# 1_PowerSupply.net
KiCad netlist of a schematic drawn in Altium Designer
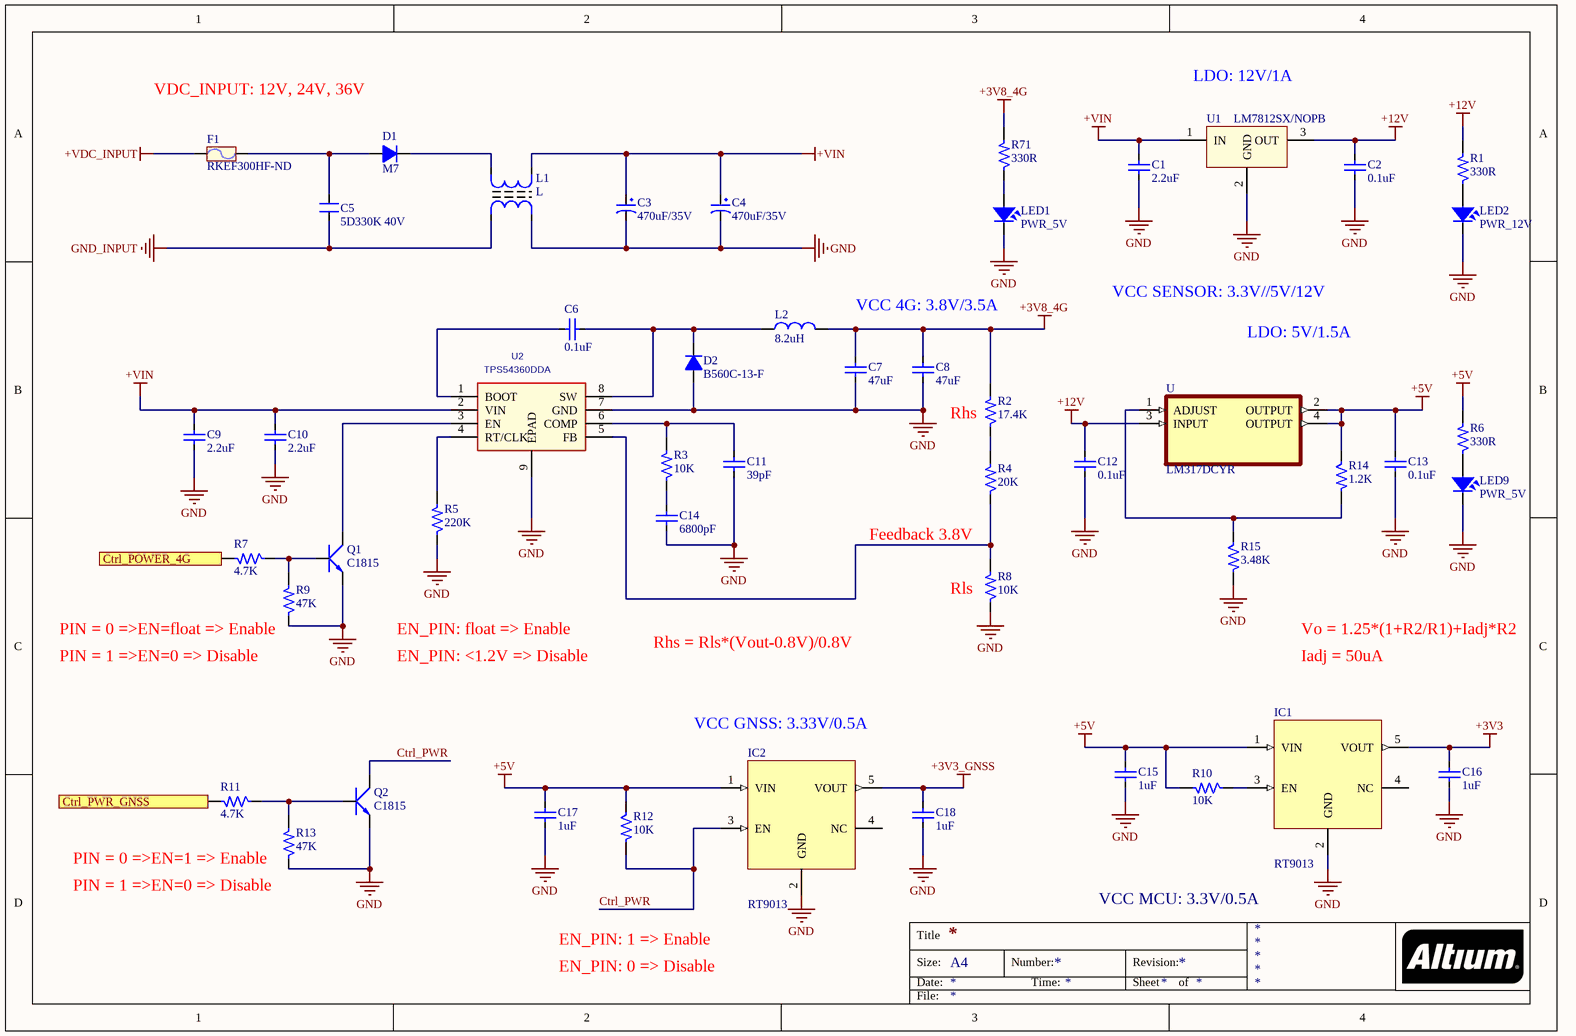
[diagram p0: [1]PowerSupply.SchDoc]

(export (version "E")
  (design (tool "Eeschema 10.0.6"))
  (components
    (comp (ref "C1")
      (value "2.2uF")
      (footprint "CAP_0805")
      (description "Capacitor")
      (fields (field (name "PUBLISHER") "Altium Limited"))
      (libsource (lib "My Library") (part "CapSMD"))
    )
    (comp (ref "C2")
      (value "0.1uF")
      (footprint "CAP_0805")
      (description "Capacitor")
      (fields (field (name "PUBLISHER") "Altium Limited"))
      (libsource (lib "My Library") (part "CapSMD"))
    )
    (comp (ref "C3")
      (value "470uF/35V")
      (footprint "C10mm")
      (description "Cap 1000uF/16V - 220uF/50V")
      (libsource (lib "GPS_Traking_V1_1") (part "CP4"))
    )
    (comp (ref "C4")
      (value "470uF/35V")
      (footprint "C10mm")
      (description "Cap 1000uF/16V - 220uF/50V")
      (libsource (lib "GPS_Traking_V1_1") (part "CP4"))
    )
    (comp (ref "C5")
      (value "5D330K 40V")
      (footprint "CN2")
      (description "5D330K 33V")
      (fields (field (name "DESIGNED BY") "VanDungEvn"))
      (libsource (lib "GPS_Traking_V1_1") (part "CN"))
    )
    (comp (ref "C6")
      (value "0.1uF")
      (footprint "CAP_0805")
      (description "Capacitor")
      (fields (field (name "PUBLISHER") "Altium Limited"))
      (libsource (lib "My Library") (part "CapSMD"))
    )
    (comp (ref "C7")
      (value "47uF")
      (footprint "CAP_0805")
      (description "Capacitor")
      (fields (field (name "PUBLISHER") "Altium Limited"))
      (libsource (lib "My Library") (part "CapSMD"))
    )
    (comp (ref "C8")
      (value "47uF")
      (footprint "CAP_0805")
      (description "Capacitor")
      (fields (field (name "PUBLISHER") "Altium Limited"))
      (libsource (lib "My Library") (part "CapSMD"))
    )
    (comp (ref "C9")
      (value "2.2uF")
      (footprint "CAP_0805")
      (description "Capacitor")
      (fields (field (name "PUBLISHER") "Altium Limited"))
      (libsource (lib "My Library") (part "CapSMD"))
    )
    (comp (ref "C10")
      (value "2.2uF")
      (footprint "CAP_0805")
      (description "Capacitor")
      (fields (field (name "PUBLISHER") "Altium Limited"))
      (libsource (lib "My Library") (part "CapSMD"))
    )
    (comp (ref "C11")
      (value "39pF")
      (footprint "CAP_0805")
      (description "Capacitor")
      (fields (field (name "PUBLISHER") "Altium Limited"))
      (libsource (lib "My Library") (part "CapSMD"))
    )
    (comp (ref "C12")
      (value "0.1uF")
      (footprint "CAP_0805")
      (description "Capacitor")
      (fields (field (name "PUBLISHER") "Altium Limited"))
      (libsource (lib "My Library") (part "CapSMD"))
    )
    (comp (ref "C13")
      (value "0.1uF")
      (footprint "CAP_0805")
      (description "Capacitor")
      (fields (field (name "PUBLISHER") "Altium Limited"))
      (libsource (lib "My Library") (part "CapSMD"))
    )
    (comp (ref "C14")
      (value "6800pF")
      (footprint "CAP_0805")
      (description "Capacitor")
      (fields (field (name "PUBLISHER") "Altium Limited"))
      (libsource (lib "My Library") (part "CapSMD"))
    )
    (comp (ref "C15")
      (value "1uF")
      (footprint "CAP_0805")
      (description "Capacitor")
      (fields (field (name "PUBLISHER") "Altium Limited"))
      (libsource (lib "My Library") (part "CapSMD"))
    )
    (comp (ref "C16")
      (value "1uF")
      (footprint "CAP_0805")
      (description "Capacitor")
      (fields (field (name "PUBLISHER") "Altium Limited"))
      (libsource (lib "My Library") (part "CapSMD"))
    )
    (comp (ref "C17")
      (value "1uF")
      (footprint "CAP_0805")
      (description "Capacitor")
      (fields (field (name "PUBLISHER") "Altium Limited"))
      (libsource (lib "My Library") (part "CapSMD"))
    )
    (comp (ref "C18")
      (value "1uF")
      (footprint "CAP_0805")
      (description "Capacitor")
      (fields (field (name "PUBLISHER") "Altium Limited"))
      (libsource (lib "My Library") (part "CapSMD"))
    )
    (comp (ref "D1")
      (value "M7")
      (footprint "SMA11")
      (description "Diode 1A")
      (libsource (lib "Anh_Trung") (part "D1A"))
    )
    (comp (ref "D2")
      (value "B560C-13-F")
      (footprint "DO-214AB SMC")
      (description "DIODE SCHOTTKY 60V 5A SMC")
      (libsource (lib "GPS_Traking_V1_1") (part "D5A"))
    )
    (comp (ref "F1")
      (value "RKEF300HF-ND")
      (footprint "FUSE2")
      (description "PTC RESET FUSE 60V 3A RADIAL")
      (fields (field (name "DESIGNED BY") "VanDungEvn"))
      (libsource (lib "GPS_Traking_V1_1") (part "Fuse"))
    )
    (comp (ref "IC1")
      (value "RT9013")
      (footprint "SOT23-5")
      (description "RT9013-33GB IC REG LINEAR 3.3V 500mA SOT23-5")
      (libsource (lib "My Library") (part "RT9013"))
    )
    (comp (ref "IC2")
      (value "RT9013")
      (footprint "SOT23-5")
      (description "RT9013-33GB IC REG LINEAR 3.3V 500mA SOT23-5")
      (libsource (lib "My Library") (part "RT9013"))
    )
    (comp (ref "L1")
      (value "L")
      (footprint "L2 UF9.8")
      (description "Inductor")
      (fields (field (name "DESIGNED BY") "VanDungEvn"))
      (libsource (lib "GPS_Traking_V1_1") (part "L2x220"))
    )
    (comp (ref "L2")
      (value "8.2uH")
      (footprint "L01 SMD 12*12*6")
      (description "FIXED IND 6.2UH 5.7A 22.4 MOHM")
      (libsource (lib "GPS_Traking_V1_1") (part "L1"))
    )
    (comp (ref "LED1")
      (value "PWR_5V")
      (footprint "LED-0805-Blue")
      (description "LED Single colour Green and Red")
      (libsource (lib "My Library") (part "LED"))
    )
    (comp (ref "LED2")
      (value "PWR_12V")
      (footprint "LED-0805-Blue")
      (description "LED Single colour Green and Red")
      (libsource (lib "My Library") (part "LED"))
    )
    (comp (ref "LED9")
      (value "PWR_5V")
      (footprint "LED-0805-Blue")
      (description "LED Single colour Green and Red")
      (libsource (lib "My Library") (part "LED"))
    )
    (comp (ref "Q1")
      (value "C1815")
      (footprint "SOT23B")
      (description "NPN 600mW, ECB")
      (libsource (lib "GPS_Traking_V1_1") (part "C1815"))
    )
    (comp (ref "Q2")
      (value "C1815")
      (footprint "SOT23B")
      (description "NPN 600mW, ECB")
      (libsource (lib "GPS_Traking_V1_1") (part "C1815"))
    )
    (comp (ref "R1")
      (value "330R")
      (footprint "R0805")
      (description "Resistor SMD")
      (libsource (lib "GPS_Traking_V1_1") (part "RM"))
    )
    (comp (ref "R2")
      (value "17.4K")
      (footprint "R0805")
      (description "Resistor SMD")
      (libsource (lib "GPS_Traking_V1_1") (part "RM"))
    )
    (comp (ref "R3")
      (value "10K")
      (footprint "R0805")
      (description "Resistor SMD")
      (libsource (lib "GPS_Traking_V1_1") (part "RM"))
    )
    (comp (ref "R4")
      (value "20K")
      (footprint "R0805")
      (description "Resistor SMD")
      (libsource (lib "GPS_Traking_V1_1") (part "RM"))
    )
    (comp (ref "R5")
      (value "220K")
      (footprint "R0805")
      (description "Resistor SMD")
      (libsource (lib "GPS_Traking_V1_1") (part "RM"))
    )
    (comp (ref "R6")
      (value "330R")
      (footprint "R0805")
      (description "Resistor SMD")
      (libsource (lib "GPS_Traking_V1_1") (part "RM"))
    )
    (comp (ref "R7")
      (value "4.7K")
      (footprint "R0805")
      (description "Resistor SMD")
      (libsource (lib "GPS_Traking_V1_1") (part "RM"))
    )
    (comp (ref "R8")
      (value "10K")
      (footprint "R0805")
      (description "Resistor SMD")
      (libsource (lib "GPS_Traking_V1_1") (part "RM"))
    )
    (comp (ref "R9")
      (value "47K")
      (footprint "R0805")
      (description "Resistor SMD")
      (libsource (lib "GPS_Traking_V1_1") (part "RM"))
    )
    (comp (ref "R10")
      (value "10K")
      (footprint "R0805")
      (description "Resistor SMD")
      (libsource (lib "GPS_Traking_V1_1") (part "RM"))
    )
    (comp (ref "R11")
      (value "4.7K")
      (footprint "R0805")
      (description "Resistor SMD")
      (libsource (lib "GPS_Traking_V1_1") (part "RM"))
    )
    (comp (ref "R12")
      (value "10K")
      (footprint "R0805")
      (description "Resistor SMD")
      (libsource (lib "GPS_Traking_V1_1") (part "RM"))
    )
    (comp (ref "R13")
      (value "47K")
      (footprint "R0805")
      (description "Resistor SMD")
      (libsource (lib "GPS_Traking_V1_1") (part "RM"))
    )
    (comp (ref "R14")
      (value "1.2K")
      (footprint "R0805")
      (description "Resistor SMD")
      (libsource (lib "GPS_Traking_V1_1") (part "RM"))
    )
    (comp (ref "R15")
      (value "3.48K")
      (footprint "R0805")
      (description "Resistor SMD")
      (libsource (lib "GPS_Traking_V1_1") (part "RM"))
    )
    (comp (ref "R71")
      (value "330R")
      (footprint "R0805")
      (description "Resistor SMD")
      (libsource (lib "GPS_Traking_V1_1") (part "RM"))
    )
    (comp (ref "U")
      (value "LM317DCYR")
      (footprint "SOT230P700X180-4N")
      (description "1.5-A, 40-V, adjustable linear voltage regulator 4-SOT-223 0 to 125")
      (fields (field (name "MF") "Texas Instruments"))
      (libsource (lib "LM317DCYR") (part "LM317DCYR"))
    )
    (comp (ref "U1")
      (value "LM7812SX/NOPB")
      (footprint "QTO-220")
      (libsource (lib "GPS_Traking_V1_1") (part "LM78xx_1"))
    )
    (comp (ref "U2")
      (value "TPS54360DDA")
      (footprint "DDA8_3P1X2P4-M")
      (description "REG BUCK SPLIT RAIL 8SOPWRPAD")
      (libsource (lib "GPS_Traking_V1_1") (part "TPS54360DDA"))
    )
  )
  (nets
    (net (code "1") (name "+3V3") (class "Default")
      (node (ref "C16") (pin "2") (pinfunction "2_2") (pintype "passive"))
      (node (ref "IC1") (pin "5") (pinfunction "VOUT_5") (pintype "output"))
    )
    (net (code "2") (name "+3V3_GNSS") (class "Default")
      (node (ref "C18") (pin "2") (pinfunction "2_2") (pintype "passive"))
      (node (ref "IC2") (pin "5") (pinfunction "VOUT_5") (pintype "output"))
    )
    (net (code "3") (name "+3V8_4G") (class "Default")
      (node (ref "C7") (pin "2") (pinfunction "2_2") (pintype "passive"))
      (node (ref "C8") (pin "2") (pinfunction "2_2") (pintype "passive"))
      (node (ref "L2") (pin "2") (pinfunction "2_2") (pintype "passive"))
      (node (ref "R2") (pin "2") (pinfunction "2_2") (pintype "passive"))
      (node (ref "R71") (pin "2") (pinfunction "2_2") (pintype "passive"))
    )
    (net (code "4") (name "+5V") (class "Default")
      (node (ref "C13") (pin "2") (pinfunction "2_2") (pintype "passive"))
      (node (ref "C15") (pin "2") (pinfunction "2_2") (pintype "passive"))
      (node (ref "C17") (pin "2") (pinfunction "2_2") (pintype "passive"))
      (node (ref "IC1") (pin "1") (pinfunction "VIN_1") (pintype "input"))
      (node (ref "IC2") (pin "1") (pinfunction "VIN_1") (pintype "input"))
      (node (ref "R10") (pin "2") (pinfunction "2_2") (pintype "passive"))
      (node (ref "R12") (pin "1") (pinfunction "1_1") (pintype "passive"))
      (node (ref "R14") (pin "1") (pinfunction "1_1") (pintype "passive"))
      (node (ref "R6") (pin "2") (pinfunction "2_2") (pintype "passive"))
      (node (ref "U") (pin "2") (pinfunction "OUTPUT_2") (pintype "output"))
      (node (ref "U") (pin "4") (pinfunction "OUTPUT_4") (pintype "output"))
    )
    (net (code "5") (name "+12V") (class "Default")
      (node (ref "C12") (pin "2") (pinfunction "2_2") (pintype "passive"))
      (node (ref "C2") (pin "2") (pinfunction "2_2") (pintype "passive"))
      (node (ref "R1") (pin "2") (pinfunction "2_2") (pintype "passive"))
      (node (ref "U") (pin "3") (pinfunction "INPUT_3") (pintype "input"))
      (node (ref "U1") (pin "3") (pinfunction "OUT_3") (pintype "passive"))
    )
    (net (code "6") (name "+VDC_INPUT") (class "Default")
      (node (ref "F1") (pin "1") (pinfunction "1_1") (pintype "passive"))
    )
    (net (code "7") (name "+VIN") (class "Default")
      (node (ref "C1") (pin "2") (pinfunction "2_2") (pintype "passive"))
      (node (ref "C10") (pin "2") (pinfunction "2_2") (pintype "passive"))
      (node (ref "C3") (pin "1") (pinfunction "1_1") (pintype "passive"))
      (node (ref "C4") (pin "1") (pinfunction "1_1") (pintype "passive"))
      (node (ref "C9") (pin "2") (pinfunction "2_2") (pintype "passive"))
      (node (ref "L1") (pin "3") (pinfunction "3_3") (pintype "passive"))
      (node (ref "U1") (pin "1") (pinfunction "IN_1") (pintype "passive"))
      (node (ref "U2") (pin "2") (pinfunction "VIN_2") (pintype "passive"))
    )
    (net (code "8") (name "/Ctrl_POWER_4G") (class "Default")
      (node (ref "R7") (pin "2") (pinfunction "2_2") (pintype "passive"))
    )
    (net (code "9") (name "/Ctrl_PWR") (class "Default")
      (node (ref "IC2") (pin "3") (pinfunction "EN_3") (pintype "input"))
      (node (ref "Q2") (pin "2") (pinfunction "C_2") (pintype "passive"))
      (node (ref "R12") (pin "2") (pinfunction "2_2") (pintype "passive"))
    )
    (net (code "10") (name "/Ctrl_PWR_GNSS") (class "Default")
      (node (ref "R11") (pin "2") (pinfunction "2_2") (pintype "passive"))
    )
    (net (code "11") (name "GND") (class "Default")
      (node (ref "C1") (pin "1") (pinfunction "1_1") (pintype "passive"))
      (node (ref "C10") (pin "1") (pinfunction "1_1") (pintype "passive"))
      (node (ref "C11") (pin "1") (pinfunction "1_1") (pintype "passive"))
      (node (ref "C12") (pin "1") (pinfunction "1_1") (pintype "passive"))
      (node (ref "C13") (pin "1") (pinfunction "1_1") (pintype "passive"))
      (node (ref "C14") (pin "1") (pinfunction "1_1") (pintype "passive"))
      (node (ref "C15") (pin "1") (pinfunction "1_1") (pintype "passive"))
      (node (ref "C16") (pin "1") (pinfunction "1_1") (pintype "passive"))
      (node (ref "C17") (pin "1") (pinfunction "1_1") (pintype "passive"))
      (node (ref "C18") (pin "1") (pinfunction "1_1") (pintype "passive"))
      (node (ref "C2") (pin "1") (pinfunction "1_1") (pintype "passive"))
      (node (ref "C3") (pin "2") (pinfunction "2_2") (pintype "passive"))
      (node (ref "C4") (pin "2") (pinfunction "2_2") (pintype "passive"))
      (node (ref "C7") (pin "1") (pinfunction "1_1") (pintype "passive"))
      (node (ref "C8") (pin "1") (pinfunction "1_1") (pintype "passive"))
      (node (ref "C9") (pin "1") (pinfunction "1_1") (pintype "passive"))
      (node (ref "D2") (pin "1") (pinfunction "A_1") (pintype "passive"))
      (node (ref "IC1") (pin "2") (pinfunction "GND_2") (pintype "passive"))
      (node (ref "IC2") (pin "2") (pinfunction "GND_2") (pintype "passive"))
      (node (ref "L1") (pin "2") (pinfunction "2_2") (pintype "passive"))
      (node (ref "LED1") (pin "2") (pinfunction "2_2") (pintype "passive"))
      (node (ref "LED2") (pin "2") (pinfunction "2_2") (pintype "passive"))
      (node (ref "LED9") (pin "2") (pinfunction "2_2") (pintype "passive"))
      (node (ref "Q1") (pin "1") (pinfunction "E_1") (pintype "passive"))
      (node (ref "Q2") (pin "1") (pinfunction "E_1") (pintype "passive"))
      (node (ref "R13") (pin "1") (pinfunction "1_1") (pintype "passive"))
      (node (ref "R15") (pin "2") (pinfunction "2_2") (pintype "passive"))
      (node (ref "R5") (pin "1") (pinfunction "1_1") (pintype "passive"))
      (node (ref "R8") (pin "1") (pinfunction "1_1") (pintype "passive"))
      (node (ref "R9") (pin "1") (pinfunction "1_1") (pintype "passive"))
      (node (ref "U1") (pin "2") (pinfunction "GND_2") (pintype "passive"))
      (node (ref "U2") (pin "7") (pinfunction "GND_7") (pintype "passive"))
      (node (ref "U2") (pin "9") (pinfunction "EPAD_9") (pintype "passive"))
    )
    (net (code "12") (name "GND_INPUT") (class "Default")
      (node (ref "C5") (pin "1") (pinfunction "1_1") (pintype "passive"))
      (node (ref "L1") (pin "1") (pinfunction "1_1") (pintype "passive"))
    )
    (net (code "13") (name "Net-(C14-Pad2)") (class "Default")
      (node (ref "C14") (pin "2") (pinfunction "2_2") (pintype "passive"))
      (node (ref "R3") (pin "1") (pinfunction "1_1") (pintype "passive"))
    )
    (net (code "14") (name "Net-(D1-A)") (class "Default")
      (node (ref "C5") (pin "2") (pinfunction "2_2") (pintype "passive"))
      (node (ref "D1") (pin "1") (pinfunction "A_1") (pintype "passive"))
      (node (ref "F1") (pin "2") (pinfunction "2_2") (pintype "passive"))
    )
    (net (code "15") (name "Net-(D1-K)") (class "Default")
      (node (ref "D1") (pin "2") (pinfunction "K_2") (pintype "passive"))
      (node (ref "L1") (pin "4") (pinfunction "4_4") (pintype "passive"))
    )
    (net (code "16") (name "Net-(D2-K)") (class "Default")
      (node (ref "C6") (pin "1") (pinfunction "1_1") (pintype "passive"))
      (node (ref "D2") (pin "2") (pinfunction "K_2") (pintype "passive"))
      (node (ref "L2") (pin "1") (pinfunction "1_1") (pintype "passive"))
      (node (ref "U2") (pin "8") (pinfunction "SW_8") (pintype "passive"))
    )
    (net (code "17") (name "Net-(IC1-EN)") (class "Default")
      (node (ref "IC1") (pin "3") (pinfunction "EN_3") (pintype "input"))
      (node (ref "R10") (pin "1") (pinfunction "1_1") (pintype "passive"))
    )
    (net (code "18") (name "Net-(LED1-Pad1)") (class "Default")
      (node (ref "LED1") (pin "1") (pinfunction "1_1") (pintype "passive"))
      (node (ref "R71") (pin "1") (pinfunction "1_1") (pintype "passive"))
    )
    (net (code "19") (name "Net-(LED2-Pad1)") (class "Default")
      (node (ref "LED2") (pin "1") (pinfunction "1_1") (pintype "passive"))
      (node (ref "R1") (pin "1") (pinfunction "1_1") (pintype "passive"))
    )
    (net (code "20") (name "Net-(LED9-Pad1)") (class "Default")
      (node (ref "LED9") (pin "1") (pinfunction "1_1") (pintype "passive"))
      (node (ref "R6") (pin "1") (pinfunction "1_1") (pintype "passive"))
    )
    (net (code "21") (name "Net-(Q1-B)") (class "Default")
      (node (ref "Q1") (pin "3") (pinfunction "B_3") (pintype "passive"))
      (node (ref "R7") (pin "1") (pinfunction "1_1") (pintype "passive"))
      (node (ref "R9") (pin "2") (pinfunction "2_2") (pintype "passive"))
    )
    (net (code "22") (name "Net-(Q1-C)") (class "Default")
      (node (ref "Q1") (pin "2") (pinfunction "C_2") (pintype "passive"))
      (node (ref "U2") (pin "3") (pinfunction "EN_3") (pintype "passive"))
    )
    (net (code "23") (name "Net-(Q2-B)") (class "Default")
      (node (ref "Q2") (pin "3") (pinfunction "B_3") (pintype "passive"))
      (node (ref "R11") (pin "1") (pinfunction "1_1") (pintype "passive"))
      (node (ref "R13") (pin "2") (pinfunction "2_2") (pintype "passive"))
    )
    (net (code "24") (name "Net-(R2-Pad1)") (class "Default")
      (node (ref "R2") (pin "1") (pinfunction "1_1") (pintype "passive"))
      (node (ref "R4") (pin "2") (pinfunction "2_2") (pintype "passive"))
    )
    (net (code "25") (name "Net-(U-ADJUST)") (class "Default")
      (node (ref "R14") (pin "2") (pinfunction "2_2") (pintype "passive"))
      (node (ref "R15") (pin "1") (pinfunction "1_1") (pintype "passive"))
      (node (ref "U") (pin "1") (pinfunction "ADJUST_1") (pintype "input"))
    )
    (net (code "26") (name "Net-(U2-BOOT)") (class "Default")
      (node (ref "C6") (pin "2") (pinfunction "2_2") (pintype "passive"))
      (node (ref "U2") (pin "1") (pinfunction "BOOT_1") (pintype "passive"))
    )
    (net (code "27") (name "Net-(U2-COMP)") (class "Default")
      (node (ref "C11") (pin "2") (pinfunction "2_2") (pintype "passive"))
      (node (ref "R3") (pin "2") (pinfunction "2_2") (pintype "passive"))
      (node (ref "U2") (pin "6") (pinfunction "COMP_6") (pintype "passive"))
    )
    (net (code "28") (name "Net-(U2-FB)") (class "Default")
      (node (ref "R4") (pin "1") (pinfunction "1_1") (pintype "passive"))
      (node (ref "R8") (pin "2") (pinfunction "2_2") (pintype "passive"))
      (node (ref "U2") (pin "5") (pinfunction "FB_5") (pintype "passive"))
    )
    (net (code "29") (name "Net-(U2-RT{slash}CLK)") (class "Default")
      (node (ref "R5") (pin "2") (pinfunction "2_2") (pintype "passive"))
      (node (ref "U2") (pin "4") (pinfunction "RT/CLK_4") (pintype "passive"))
    )
    (net (code "30") (name "unconnected-(IC1-NC-Pad4)") (class "Default")
      (node (ref "IC1") (pin "4") (pinfunction "NC_4") (pintype "passive"))
    )
    (net (code "31") (name "unconnected-(IC2-NC-Pad4)") (class "Default")
      (node (ref "IC2") (pin "4") (pinfunction "NC_4") (pintype "passive"))
    )
  )
)
